# pi3-MotherBoard-rev2.net
KiCad netlist of a schematic drawn in EAGLE
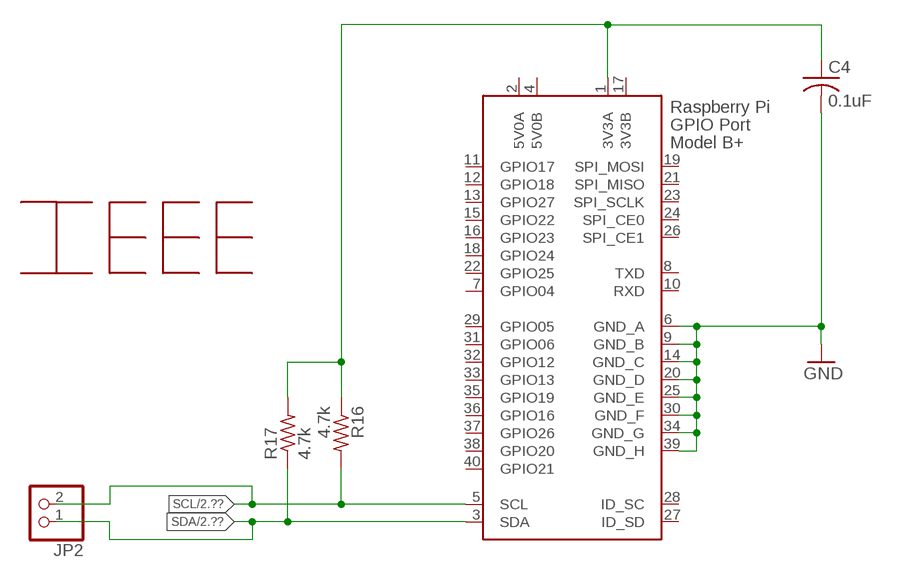
[diagram p0: schematic, sheet 1]
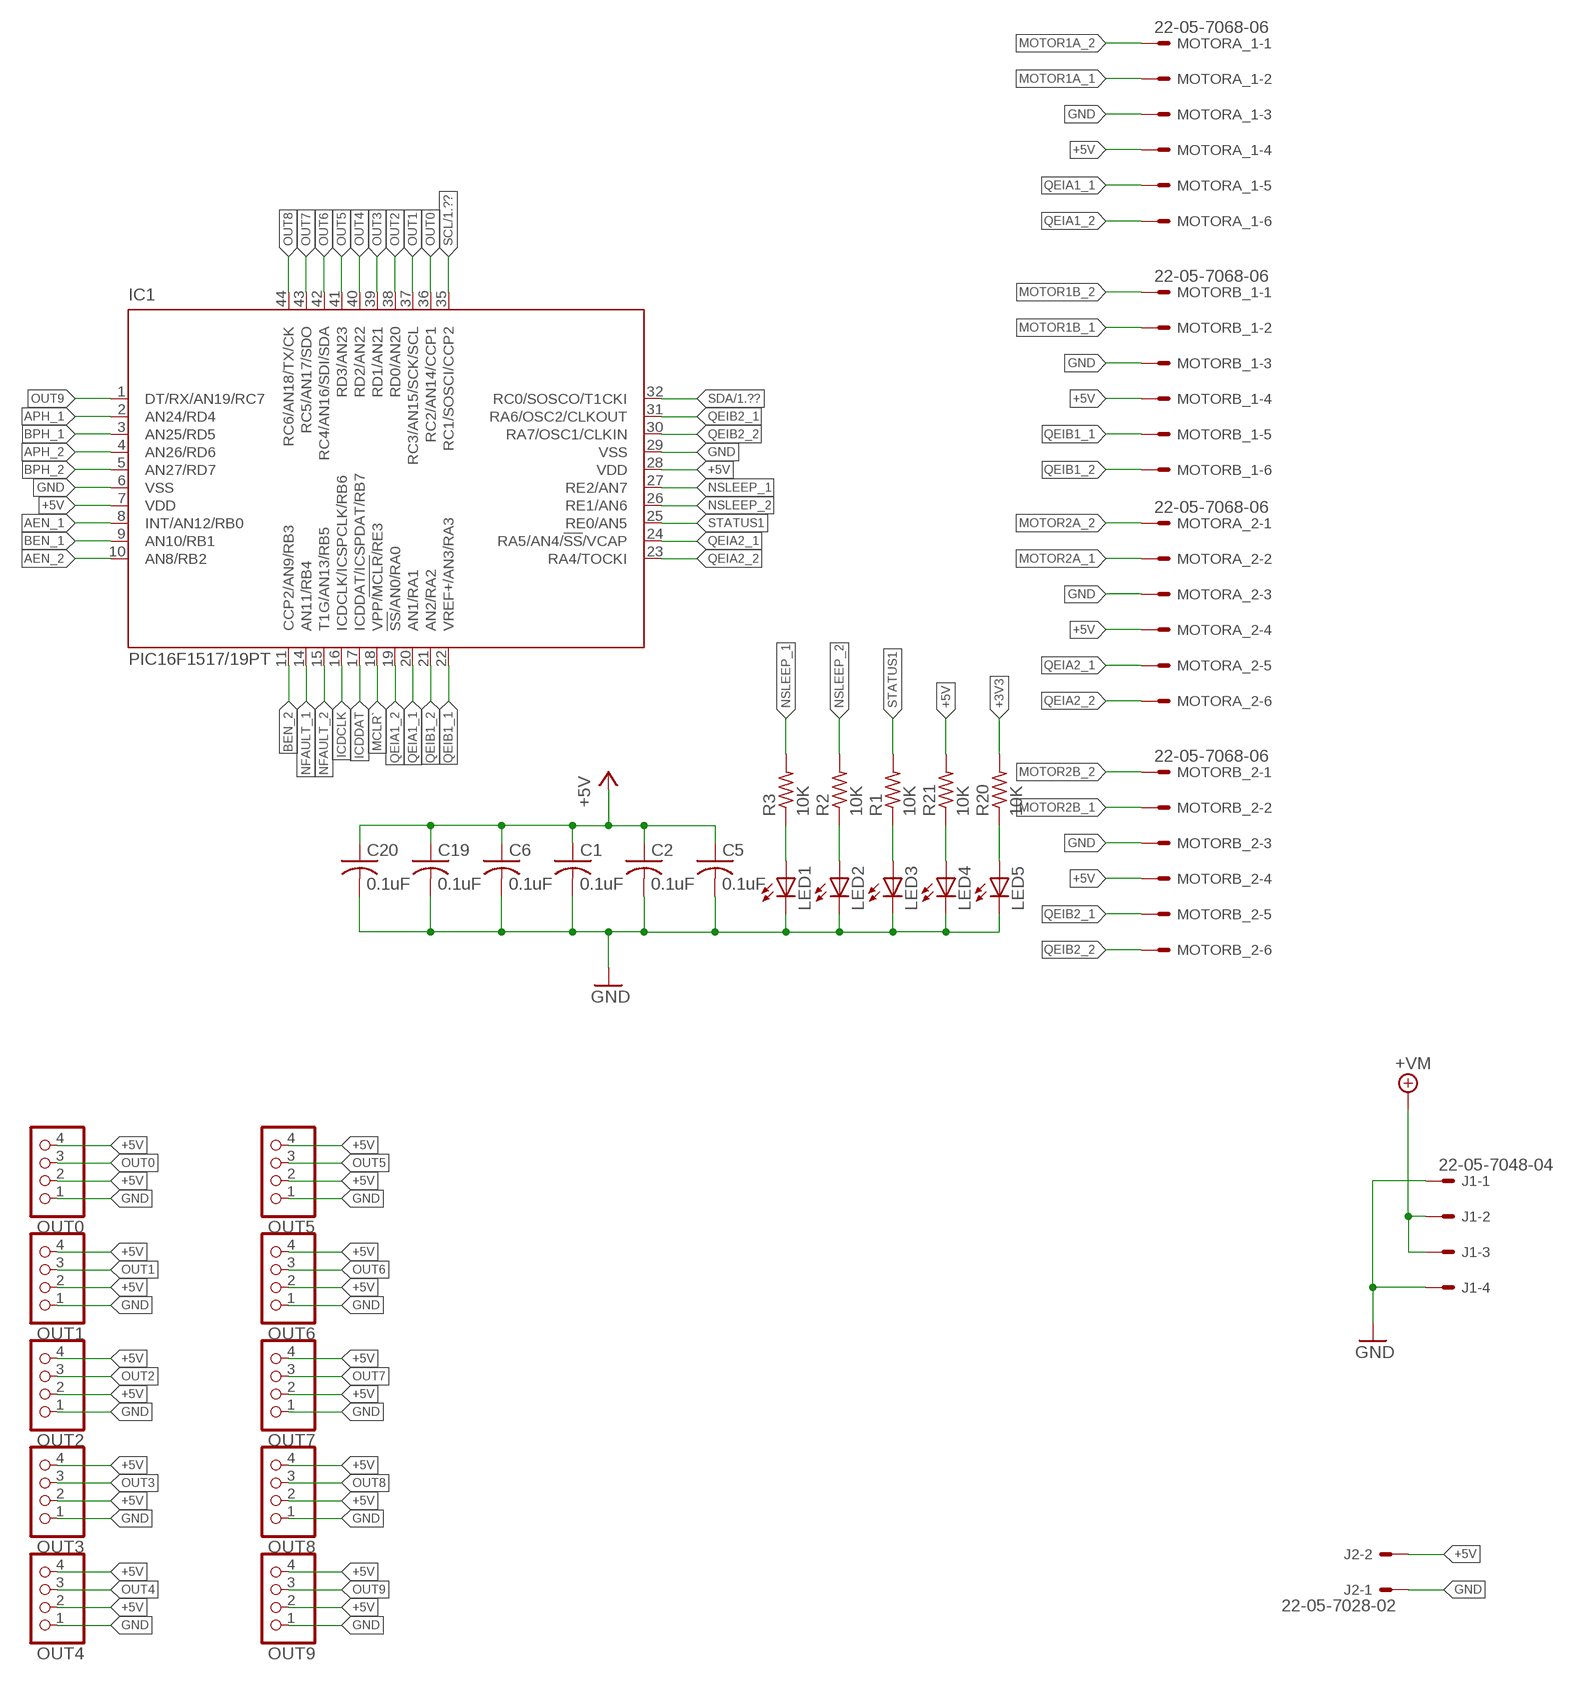
[diagram p1: schematic, sheet 2, part 1 of 2]
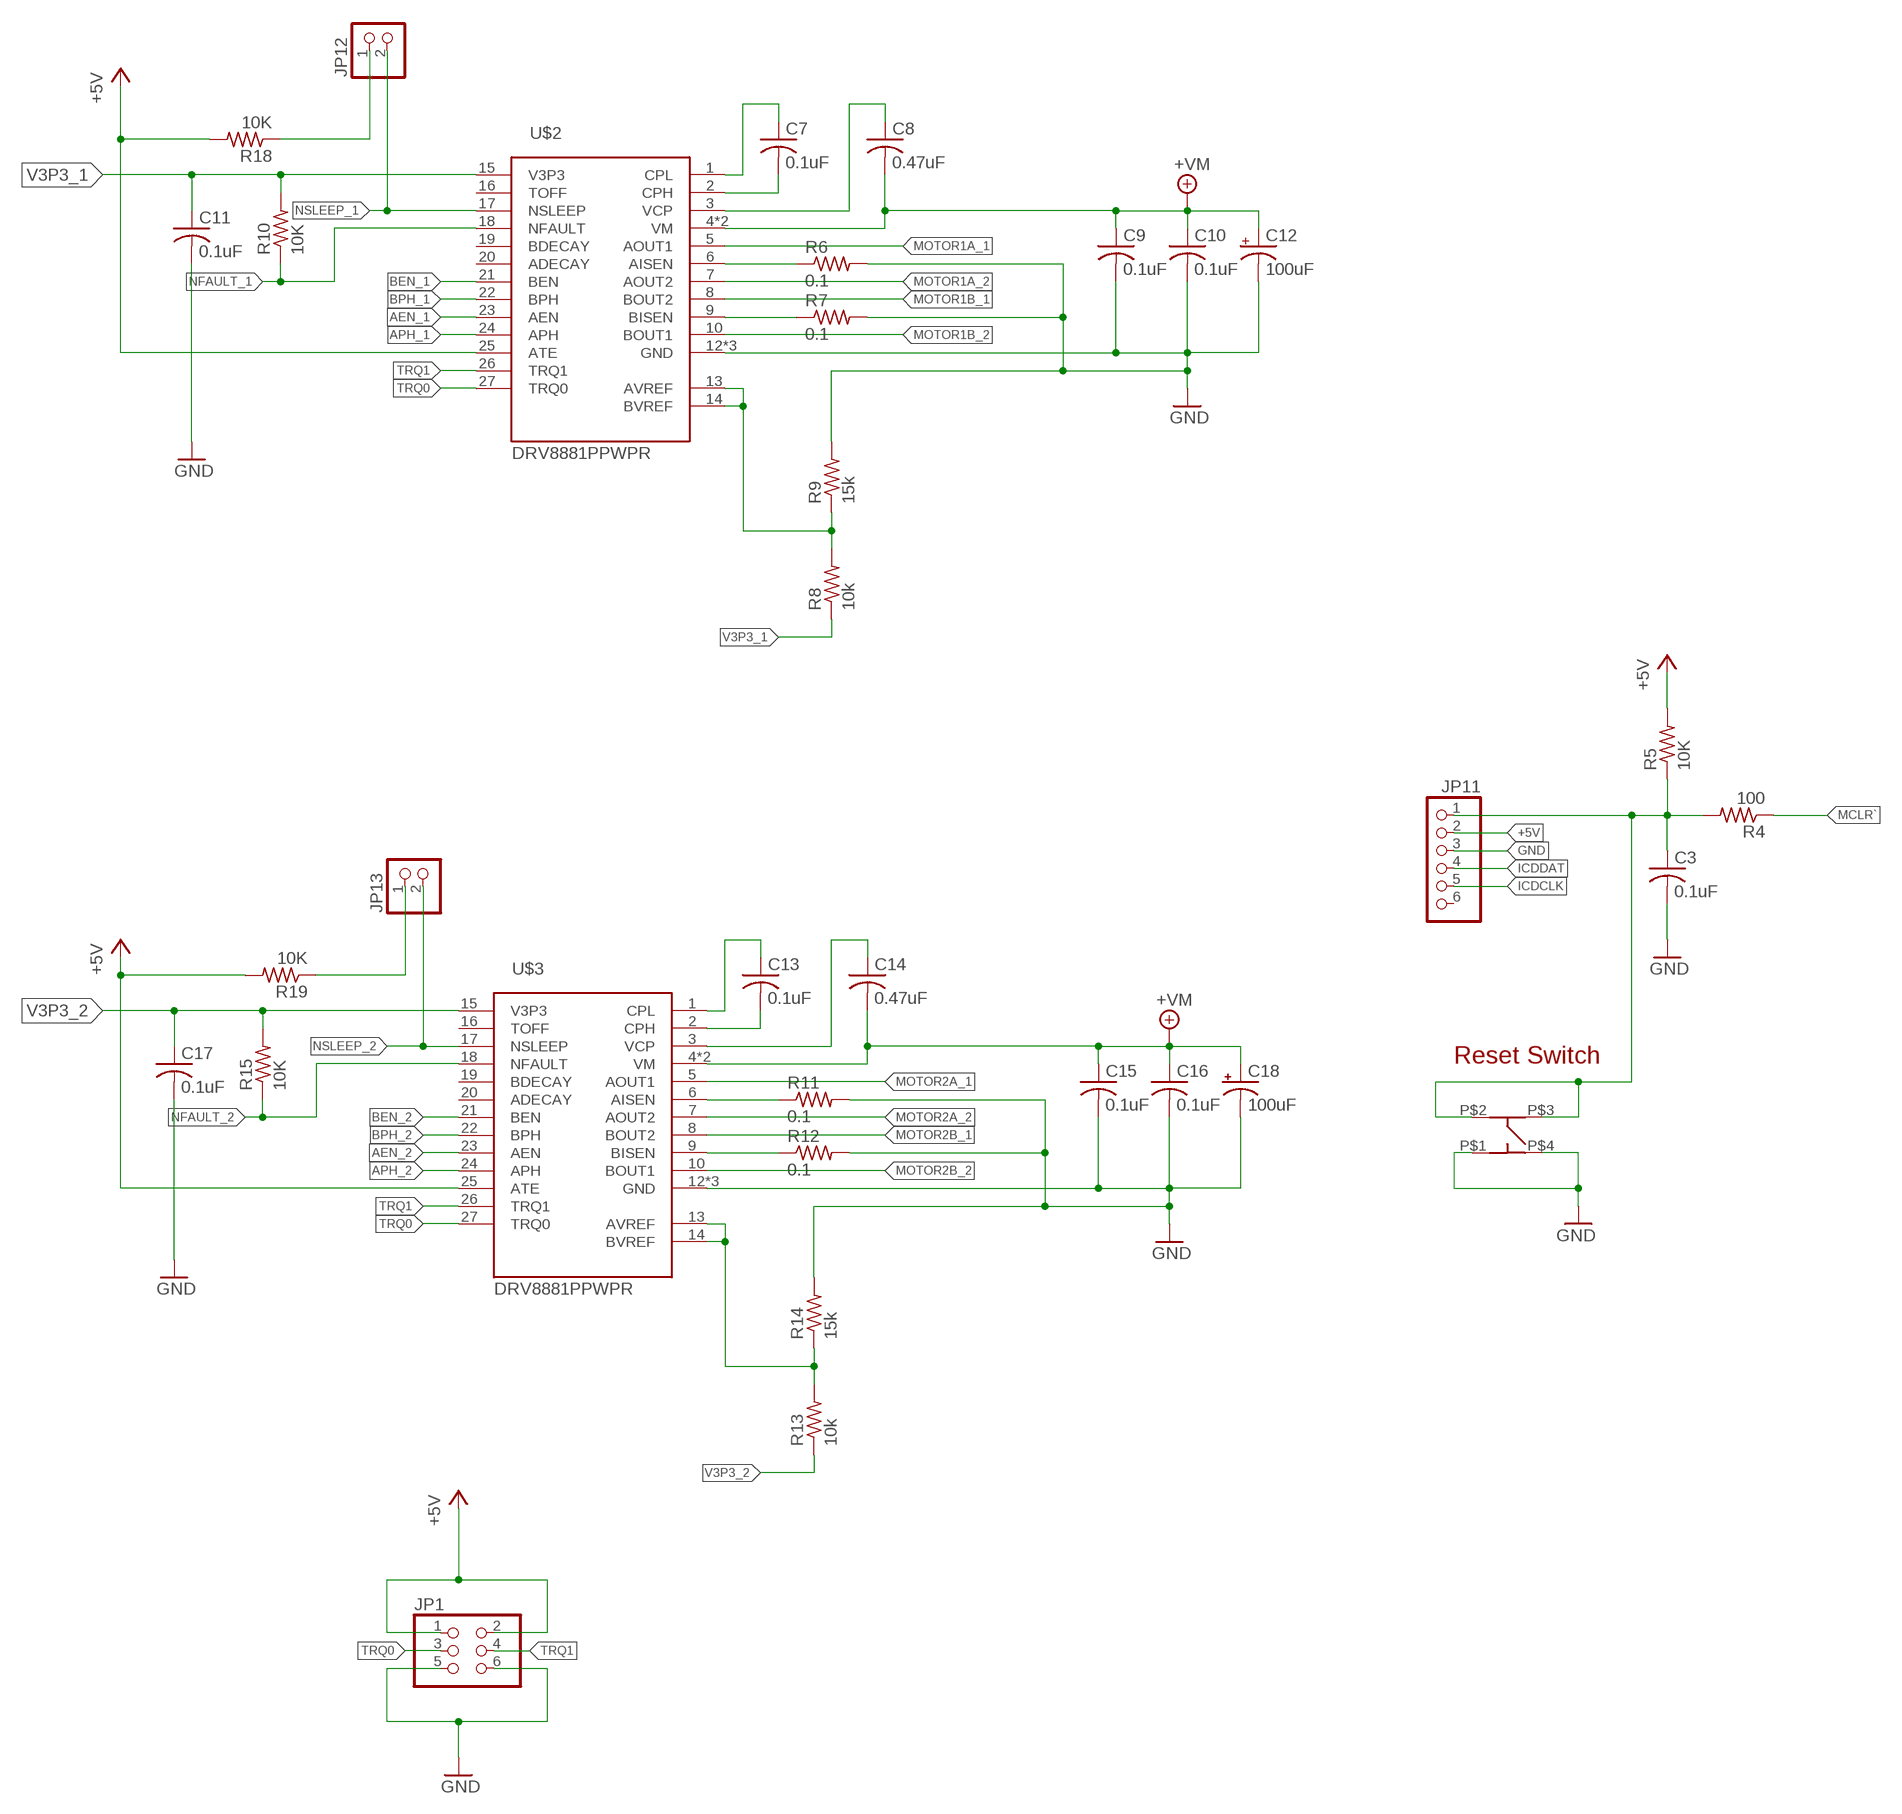
[diagram p2: schematic, sheet 2, part 2 of 2]

(export (version "E")
  (design (tool "Eeschema 10.0.6"))
  (components
    (comp (ref "C4")
      (value "0.1uF")
      (footprint "eagle-import:C0805")
      (libsource (lib "eagle-import") (part "C-USC0805"))
    )
    (comp (ref "JP2")
      (value "PINHD-1X2")
      (footprint "eagle-import:1X02")
      (libsource (lib "eagle-import") (part "PINHD-1X2"))
    )
    (comp (ref "R16")
      (value "4.7k")
      (footprint "eagle-import:R1206")
      (libsource (lib "eagle-import") (part "R-US_R1206"))
    )
    (comp (ref "R17")
      (value "4.7k")
      (footprint "eagle-import:R1206")
      (libsource (lib "eagle-import") (part "R-US_R1206"))
    )
    (comp (ref "U$1")
      (value "LOGO")
      (footprint "eagle-import:IEEE-LOGO")
      (libsource (lib "eagle-import") (part "LOGO"))
    )
    (comp (ref "X1")
      (value "RASPI_BOARD_B+#_FP")
      (footprint "eagle-import:RASPI_BOARD_B+_FULL_PAD")
      (libsource (lib "eagle-import") (part "RASPI_BOARD_B+#_FP"))
    )
    (comp (ref "C1")
      (value "0.1uF")
      (footprint "eagle-import:C0805")
      (libsource (lib "eagle-import") (part "C-USC0805"))
    )
    (comp (ref "C2")
      (value "0.1uF")
      (footprint "eagle-import:C0805")
      (libsource (lib "eagle-import") (part "C-USC0805"))
    )
    (comp (ref "C3")
      (value "0.1uF")
      (footprint "eagle-import:C0805")
      (libsource (lib "eagle-import") (part "C-USC0805"))
    )
    (comp (ref "C5")
      (value "0.1uF")
      (footprint "eagle-import:C0805")
      (libsource (lib "eagle-import") (part "C-USC0805"))
    )
    (comp (ref "C6")
      (value "0.1uF")
      (footprint "eagle-import:C0805")
      (libsource (lib "eagle-import") (part "C-USC0805"))
    )
    (comp (ref "C7")
      (value "0.1uF")
      (footprint "eagle-import:C0402")
      (libsource (lib "eagle-import") (part "C-USC0402"))
    )
    (comp (ref "C8")
      (value "0.47uF")
      (footprint "eagle-import:C0402")
      (libsource (lib "eagle-import") (part "C-USC0402"))
    )
    (comp (ref "C9")
      (value "0.1uF")
      (footprint "eagle-import:C0402")
      (libsource (lib "eagle-import") (part "C-USC0402"))
    )
    (comp (ref "C10")
      (value "0.1uF")
      (footprint "eagle-import:C0402")
      (libsource (lib "eagle-import") (part "C-USC0402"))
    )
    (comp (ref "C11")
      (value "0.1uF")
      (footprint "eagle-import:C0402")
      (libsource (lib "eagle-import") (part "C-USC0402"))
    )
    (comp (ref "C12")
      (value "100uF")
      (footprint "eagle-import:EIA7343")
      (libsource (lib "eagle-import") (part "100UF-10V-10%(TANT)"))
    )
    (comp (ref "C13")
      (value "0.1uF")
      (footprint "eagle-import:C0402")
      (libsource (lib "eagle-import") (part "C-USC0402"))
    )
    (comp (ref "C14")
      (value "0.47uF")
      (footprint "eagle-import:C0402")
      (libsource (lib "eagle-import") (part "C-USC0402"))
    )
    (comp (ref "C15")
      (value "0.1uF")
      (footprint "eagle-import:C0402")
      (libsource (lib "eagle-import") (part "C-USC0402"))
    )
    (comp (ref "C16")
      (value "0.1uF")
      (footprint "eagle-import:C0402")
      (libsource (lib "eagle-import") (part "C-USC0402"))
    )
    (comp (ref "C17")
      (value "0.1uF")
      (footprint "eagle-import:C0402")
      (libsource (lib "eagle-import") (part "C-USC0402"))
    )
    (comp (ref "C18")
      (value "100uF")
      (footprint "eagle-import:EIA7343")
      (libsource (lib "eagle-import") (part "100UF-10V-10%(TANT)"))
    )
    (comp (ref "C19")
      (value "0.1uF")
      (footprint "eagle-import:C0805")
      (libsource (lib "eagle-import") (part "C-USC0805"))
    )
    (comp (ref "C20")
      (value "0.1uF")
      (footprint "eagle-import:C0805")
      (libsource (lib "eagle-import") (part "C-USC0805"))
    )
    (comp (ref "IC1")
      (value "PIC16F1517/19PT")
      (footprint "eagle-import:TQFP44")
      (libsource (lib "eagle-import") (part "PIC16F1517/19PT"))
    )
    (comp (ref "J1")
      (value "22-05-7048-04")
      (footprint "eagle-import:7395-04")
      (libsource (lib "eagle-import") (part "22-?-0405-7048"))
    )
    (comp (ref "J2")
      (value "22-05-7028-02")
      (footprint "eagle-import:7395-02")
      (libsource (lib "eagle-import") (part "22-?-0205-7028"))
    )
    (comp (ref "JP1")
      (value "PINHD-2X3")
      (footprint "eagle-import:2X03")
      (libsource (lib "eagle-import") (part "PINHD-2X3"))
    )
    (comp (ref "JP11")
      (value "PINHD-1X6/90")
      (footprint "eagle-import:1X06_90")
      (libsource (lib "eagle-import") (part "PINHD-1X6/90"))
    )
    (comp (ref "JP12")
      (value "PINHD-1X2")
      (footprint "eagle-import:1X02")
      (libsource (lib "eagle-import") (part "PINHD-1X2"))
    )
    (comp (ref "JP13")
      (value "PINHD-1X2")
      (footprint "eagle-import:1X02")
      (libsource (lib "eagle-import") (part "PINHD-1X2"))
    )
    (comp (ref "LED1")
      (value "LEDSML0603")
      (footprint "eagle-import:SML0603")
      (libsource (lib "eagle-import") (part "LEDSML0603"))
    )
    (comp (ref "LED2")
      (value "LEDSML0603")
      (footprint "eagle-import:SML0603")
      (libsource (lib "eagle-import") (part "LEDSML0603"))
    )
    (comp (ref "LED3")
      (value "LEDSML0603")
      (footprint "eagle-import:SML0603")
      (libsource (lib "eagle-import") (part "LEDSML0603"))
    )
    (comp (ref "LED4")
      (value "LEDSML0603")
      (footprint "eagle-import:SML0603")
      (libsource (lib "eagle-import") (part "LEDSML0603"))
    )
    (comp (ref "LED5")
      (value "LEDSML0603")
      (footprint "eagle-import:SML0603")
      (libsource (lib "eagle-import") (part "LEDSML0603"))
    )
    (comp (ref "MOTORA_1")
      (value "22-05-7068-06")
      (footprint "eagle-import:7395-06")
      (libsource (lib "eagle-import") (part "22-?-0605-7068"))
    )
    (comp (ref "MOTORA_2")
      (value "22-05-7068-06")
      (footprint "eagle-import:7395-06")
      (libsource (lib "eagle-import") (part "22-?-0605-7068"))
    )
    (comp (ref "MOTORB_1")
      (value "22-05-7068-06")
      (footprint "eagle-import:7395-06")
      (libsource (lib "eagle-import") (part "22-?-0605-7068"))
    )
    (comp (ref "MOTORB_2")
      (value "22-05-7068-06")
      (footprint "eagle-import:7395-06")
      (libsource (lib "eagle-import") (part "22-?-0605-7068"))
    )
    (comp (ref "OUT0")
      (value "PINHD-1X4")
      (footprint "eagle-import:1X04")
      (libsource (lib "eagle-import") (part "PINHD-1X4"))
    )
    (comp (ref "OUT1")
      (value "PINHD-1X4")
      (footprint "eagle-import:1X04")
      (libsource (lib "eagle-import") (part "PINHD-1X4"))
    )
    (comp (ref "OUT2")
      (value "PINHD-1X4")
      (footprint "eagle-import:1X04")
      (libsource (lib "eagle-import") (part "PINHD-1X4"))
    )
    (comp (ref "OUT3")
      (value "PINHD-1X4")
      (footprint "eagle-import:1X04")
      (libsource (lib "eagle-import") (part "PINHD-1X4"))
    )
    (comp (ref "OUT4")
      (value "PINHD-1X4")
      (footprint "eagle-import:1X04")
      (libsource (lib "eagle-import") (part "PINHD-1X4"))
    )
    (comp (ref "OUT5")
      (value "PINHD-1X4")
      (footprint "eagle-import:1X04")
      (libsource (lib "eagle-import") (part "PINHD-1X4"))
    )
    (comp (ref "OUT6")
      (value "PINHD-1X4")
      (footprint "eagle-import:1X04")
      (libsource (lib "eagle-import") (part "PINHD-1X4"))
    )
    (comp (ref "OUT7")
      (value "PINHD-1X4")
      (footprint "eagle-import:1X04")
      (libsource (lib "eagle-import") (part "PINHD-1X4"))
    )
    (comp (ref "OUT8")
      (value "PINHD-1X4")
      (footprint "eagle-import:1X04")
      (libsource (lib "eagle-import") (part "PINHD-1X4"))
    )
    (comp (ref "OUT9")
      (value "PINHD-1X4")
      (footprint "eagle-import:1X04")
      (libsource (lib "eagle-import") (part "PINHD-1X4"))
    )
    (comp (ref "R1")
      (value "10K")
      (footprint "eagle-import:R1206")
      (libsource (lib "eagle-import") (part "R-US_R1206"))
    )
    (comp (ref "R2")
      (value "10K")
      (footprint "eagle-import:R1206")
      (libsource (lib "eagle-import") (part "R-US_R1206"))
    )
    (comp (ref "R3")
      (value "10K")
      (footprint "eagle-import:R1206")
      (libsource (lib "eagle-import") (part "R-US_R1206"))
    )
    (comp (ref "R4")
      (value "100")
      (footprint "eagle-import:R1206")
      (libsource (lib "eagle-import") (part "R-US_R1206"))
    )
    (comp (ref "R5")
      (value "10K")
      (footprint "eagle-import:R1206")
      (libsource (lib "eagle-import") (part "R-US_R1206"))
    )
    (comp (ref "R6")
      (value "0.1")
      (footprint "eagle-import:R1206")
      (libsource (lib "eagle-import") (part "R-US_R1206"))
    )
    (comp (ref "R7")
      (value "0.1")
      (footprint "eagle-import:R1206")
      (libsource (lib "eagle-import") (part "R-US_R1206"))
    )
    (comp (ref "R8")
      (value "10k")
      (footprint "eagle-import:R0402")
      (libsource (lib "eagle-import") (part "R-US_R0402"))
    )
    (comp (ref "R9")
      (value "15k")
      (footprint "eagle-import:R0402")
      (libsource (lib "eagle-import") (part "R-US_R0402"))
    )
    (comp (ref "R10")
      (value "10K")
      (footprint "eagle-import:R1206")
      (libsource (lib "eagle-import") (part "R-US_R1206"))
    )
    (comp (ref "R11")
      (value "0.1")
      (footprint "eagle-import:R1206")
      (libsource (lib "eagle-import") (part "R-US_R1206"))
    )
    (comp (ref "R12")
      (value "0.1")
      (footprint "eagle-import:R1206")
      (libsource (lib "eagle-import") (part "R-US_R1206"))
    )
    (comp (ref "R13")
      (value "10k")
      (footprint "eagle-import:R0402")
      (libsource (lib "eagle-import") (part "R-US_R0402"))
    )
    (comp (ref "R14")
      (value "15k")
      (footprint "eagle-import:R0402")
      (libsource (lib "eagle-import") (part "R-US_R0402"))
    )
    (comp (ref "R15")
      (value "10K")
      (footprint "eagle-import:R1206")
      (libsource (lib "eagle-import") (part "R-US_R1206"))
    )
    (comp (ref "R18")
      (value "10K")
      (footprint "eagle-import:R1206")
      (libsource (lib "eagle-import") (part "R-US_R1206"))
    )
    (comp (ref "R19")
      (value "10K")
      (footprint "eagle-import:R1206")
      (libsource (lib "eagle-import") (part "R-US_R1206"))
    )
    (comp (ref "R20")
      (value "10K")
      (footprint "eagle-import:R1206")
      (libsource (lib "eagle-import") (part "R-US_R1206"))
    )
    (comp (ref "R21")
      (value "10K")
      (footprint "eagle-import:R1206")
      (libsource (lib "eagle-import") (part "R-US_R1206"))
    )
    (comp (ref "TOUCH_RESET")
      (value "RESET")
      (footprint "eagle-import:MC32882_FINAL")
      (libsource (lib "eagle-import") (part "MC32882_SW"))
    )
    (comp (ref "U$2")
      (value "DRV8881PPWPR")
      (footprint "eagle-import:TSSOP-28")
      (libsource (lib "eagle-import") (part "DRV8881PPWPR"))
    )
    (comp (ref "U$3")
      (value "DRV8881PPWPR")
      (footprint "eagle-import:TSSOP-28")
      (libsource (lib "eagle-import") (part "DRV8881PPWPR"))
    )
  )
  (nets
    (net (code "1") (name "+3V3") (class "Default")
      (node (ref "C4") (pin "1") (pinfunction "1_1") (pintype "passive"))
      (node (ref "R16") (pin "1") (pinfunction "1_1") (pintype "passive"))
      (node (ref "R17") (pin "2") (pinfunction "2_2") (pintype "passive"))
      (node (ref "R20") (pin "2") (pinfunction "2_2") (pintype "passive"))
      (node (ref "X1") (pin "1") (pinfunction "3V3A_1") (pintype "power_in"))
    )
    (net (code "2") (name "+5V") (class "Default")
      (node (ref "C1") (pin "1") (pinfunction "1_1") (pintype "passive"))
      (node (ref "C19") (pin "1") (pinfunction "1_1") (pintype "passive"))
      (node (ref "C2") (pin "1") (pinfunction "1_1") (pintype "passive"))
      (node (ref "C20") (pin "1") (pinfunction "1_1") (pintype "passive"))
      (node (ref "C5") (pin "1") (pinfunction "1_1") (pintype "passive"))
      (node (ref "C6") (pin "1") (pinfunction "1_1") (pintype "passive"))
      (node (ref "IC1") (pin "28") (pinfunction "VDD_28") (pintype "power_in"))
      (node (ref "IC1") (pin "7") (pinfunction "VDD_7") (pintype "power_in"))
      (node (ref "J2") (pin "2") (pinfunction "S_2") (pintype "passive"))
      (node (ref "JP1") (pin "1") (pinfunction "1_1") (pintype "passive"))
      (node (ref "JP1") (pin "2") (pinfunction "2_2") (pintype "passive"))
      (node (ref "JP11") (pin "2") (pinfunction "2_2") (pintype "passive"))
      (node (ref "MOTORA_1") (pin "4") (pinfunction "S_4") (pintype "passive"))
      (node (ref "MOTORA_2") (pin "4") (pinfunction "S_4") (pintype "passive"))
      (node (ref "MOTORB_1") (pin "4") (pinfunction "S_4") (pintype "passive"))
      (node (ref "MOTORB_2") (pin "4") (pinfunction "S_4") (pintype "passive"))
      (node (ref "OUT0") (pin "2") (pinfunction "2_2") (pintype "passive"))
      (node (ref "OUT0") (pin "4") (pinfunction "4_4") (pintype "passive"))
      (node (ref "OUT1") (pin "2") (pinfunction "2_2") (pintype "passive"))
      (node (ref "OUT1") (pin "4") (pinfunction "4_4") (pintype "passive"))
      (node (ref "OUT2") (pin "2") (pinfunction "2_2") (pintype "passive"))
      (node (ref "OUT2") (pin "4") (pinfunction "4_4") (pintype "passive"))
      (node (ref "OUT3") (pin "2") (pinfunction "2_2") (pintype "passive"))
      (node (ref "OUT3") (pin "4") (pinfunction "4_4") (pintype "passive"))
      (node (ref "OUT4") (pin "2") (pinfunction "2_2") (pintype "passive"))
      (node (ref "OUT4") (pin "4") (pinfunction "4_4") (pintype "passive"))
      (node (ref "OUT5") (pin "2") (pinfunction "2_2") (pintype "passive"))
      (node (ref "OUT5") (pin "4") (pinfunction "4_4") (pintype "passive"))
      (node (ref "OUT6") (pin "2") (pinfunction "2_2") (pintype "passive"))
      (node (ref "OUT6") (pin "4") (pinfunction "4_4") (pintype "passive"))
      (node (ref "OUT7") (pin "2") (pinfunction "2_2") (pintype "passive"))
      (node (ref "OUT7") (pin "4") (pinfunction "4_4") (pintype "passive"))
      (node (ref "OUT8") (pin "2") (pinfunction "2_2") (pintype "passive"))
      (node (ref "OUT8") (pin "4") (pinfunction "4_4") (pintype "passive"))
      (node (ref "OUT9") (pin "2") (pinfunction "2_2") (pintype "passive"))
      (node (ref "OUT9") (pin "4") (pinfunction "4_4") (pintype "passive"))
      (node (ref "R18") (pin "2") (pinfunction "2_2") (pintype "passive"))
      (node (ref "R19") (pin "2") (pinfunction "2_2") (pintype "passive"))
      (node (ref "R21") (pin "2") (pinfunction "2_2") (pintype "passive"))
      (node (ref "R5") (pin "2") (pinfunction "2_2") (pintype "passive"))
      (node (ref "U$2") (pin "25") (pinfunction "ATE_25") (pintype "bidirectional"))
      (node (ref "U$3") (pin "25") (pinfunction "ATE_25") (pintype "bidirectional"))
    )
    (net (code "3") (name "+7V") (class "Default")
      (node (ref "C10") (pin "1") (pinfunction "1_1") (pintype "passive"))
      (node (ref "C12") (pin "A") (pinfunction "+_A") (pintype "passive"))
      (node (ref "C14") (pin "2") (pinfunction "2_2") (pintype "passive"))
      (node (ref "C15") (pin "1") (pinfunction "1_1") (pintype "passive"))
      (node (ref "C16") (pin "1") (pinfunction "1_1") (pintype "passive"))
      (node (ref "C18") (pin "A") (pinfunction "+_A") (pintype "passive"))
      (node (ref "C8") (pin "2") (pinfunction "2_2") (pintype "passive"))
      (node (ref "C9") (pin "1") (pinfunction "1_1") (pintype "passive"))
      (node (ref "J1") (pin "2") (pinfunction "S_2") (pintype "passive"))
      (node (ref "J1") (pin "3") (pinfunction "S_3") (pintype "passive"))
      (node (ref "U$2") (pin "11") (pinfunction "VM_11") (pintype "bidirectional"))
      (node (ref "U$2") (pin "4") (pinfunction "VM_4") (pintype "bidirectional"))
      (node (ref "U$3") (pin "11") (pinfunction "VM_11") (pintype "bidirectional"))
      (node (ref "U$3") (pin "4") (pinfunction "VM_4") (pintype "bidirectional"))
    )
    (net (code "4") (name "3V3B") (class "Default")
      (node (ref "X1") (pin "17") (pinfunction "3V3B_17") (pintype "power_in"))
    )
    (net (code "5") (name "5V0A") (class "Default")
      (node (ref "X1") (pin "2") (pinfunction "5V0A_2") (pintype "power_in"))
    )
    (net (code "6") (name "5V0B") (class "Default")
      (node (ref "X1") (pin "4") (pinfunction "5V0B_4") (pintype "power_in"))
    )
    (net (code "7") (name "AEN_1") (class "Default")
      (node (ref "IC1") (pin "8") (pinfunction "INT/AN12/RB0_8") (pintype "bidirectional"))
      (node (ref "U$2") (pin "23") (pinfunction "AEN_23") (pintype "bidirectional"))
    )
    (net (code "8") (name "AEN_2") (class "Default")
      (node (ref "IC1") (pin "10") (pinfunction "AN8/RB2_10") (pintype "bidirectional"))
      (node (ref "U$3") (pin "23") (pinfunction "AEN_23") (pintype "bidirectional"))
    )
    (net (code "9") (name "APH_1") (class "Default")
      (node (ref "IC1") (pin "2") (pinfunction "AN24/RD4_2") (pintype "bidirectional"))
      (node (ref "U$2") (pin "24") (pinfunction "APH_24") (pintype "bidirectional"))
    )
    (net (code "10") (name "APH_2") (class "Default")
      (node (ref "IC1") (pin "4") (pinfunction "AN26/RD6_4") (pintype "bidirectional"))
      (node (ref "U$3") (pin "24") (pinfunction "APH_24") (pintype "bidirectional"))
    )
    (net (code "11") (name "BEN_1") (class "Default")
      (node (ref "IC1") (pin "9") (pinfunction "AN10/RB1_9") (pintype "bidirectional"))
      (node (ref "U$2") (pin "21") (pinfunction "BEN_21") (pintype "bidirectional"))
    )
    (net (code "12") (name "BEN_2") (class "Default")
      (node (ref "IC1") (pin "11") (pinfunction "CCP2/AN9/RB3_11") (pintype "bidirectional"))
      (node (ref "U$3") (pin "21") (pinfunction "BEN_21") (pintype "bidirectional"))
    )
    (net (code "13") (name "BPH_1") (class "Default")
      (node (ref "IC1") (pin "3") (pinfunction "AN25/RD5_3") (pintype "bidirectional"))
      (node (ref "U$2") (pin "22") (pinfunction "BPH_22") (pintype "bidirectional"))
    )
    (net (code "14") (name "BPH_2") (class "Default")
      (node (ref "IC1") (pin "5") (pinfunction "AN27/RD7_5") (pintype "bidirectional"))
      (node (ref "U$3") (pin "22") (pinfunction "BPH_22") (pintype "bidirectional"))
    )
    (net (code "15") (name "GND") (class "Default")
      (node (ref "C1") (pin "2") (pinfunction "2_2") (pintype "passive"))
      (node (ref "C10") (pin "2") (pinfunction "2_2") (pintype "passive"))
      (node (ref "C11") (pin "2") (pinfunction "2_2") (pintype "passive"))
      (node (ref "C12") (pin "C") (pinfunction "-_C") (pintype "passive"))
      (node (ref "C15") (pin "2") (pinfunction "2_2") (pintype "passive"))
      (node (ref "C16") (pin "2") (pinfunction "2_2") (pintype "passive"))
      (node (ref "C17") (pin "2") (pinfunction "2_2") (pintype "passive"))
      (node (ref "C18") (pin "C") (pinfunction "-_C") (pintype "passive"))
      (node (ref "C19") (pin "2") (pinfunction "2_2") (pintype "passive"))
      (node (ref "C2") (pin "2") (pinfunction "2_2") (pintype "passive"))
      (node (ref "C20") (pin "2") (pinfunction "2_2") (pintype "passive"))
      (node (ref "C3") (pin "2") (pinfunction "2_2") (pintype "passive"))
      (node (ref "C4") (pin "2") (pinfunction "2_2") (pintype "passive"))
      (node (ref "C5") (pin "2") (pinfunction "2_2") (pintype "passive"))
      (node (ref "C6") (pin "2") (pinfunction "2_2") (pintype "passive"))
      (node (ref "C9") (pin "2") (pinfunction "2_2") (pintype "passive"))
      (node (ref "IC1") (pin "29") (pinfunction "VSS_29") (pintype "power_in"))
      (node (ref "IC1") (pin "6") (pinfunction "VSS_6") (pintype "power_in"))
      (node (ref "J1") (pin "1") (pinfunction "S_1") (pintype "passive"))
      (node (ref "J1") (pin "4") (pinfunction "S_4") (pintype "passive"))
      (node (ref "J2") (pin "1") (pinfunction "S_1") (pintype "passive"))
      (node (ref "JP1") (pin "5") (pinfunction "5_5") (pintype "passive"))
      (node (ref "JP1") (pin "6") (pinfunction "6_6") (pintype "passive"))
      (node (ref "JP11") (pin "3") (pinfunction "3_3") (pintype "passive"))
      (node (ref "LED1") (pin "C") (pinfunction "C_C") (pintype "passive"))
      (node (ref "LED2") (pin "C") (pinfunction "C_C") (pintype "passive"))
      (node (ref "LED3") (pin "C") (pinfunction "C_C") (pintype "passive"))
      (node (ref "LED4") (pin "C") (pinfunction "C_C") (pintype "passive"))
      (node (ref "LED5") (pin "C") (pinfunction "C_C") (pintype "passive"))
      (node (ref "MOTORA_1") (pin "3") (pinfunction "S_3") (pintype "passive"))
      (node (ref "MOTORA_2") (pin "3") (pinfunction "S_3") (pintype "passive"))
      (node (ref "MOTORB_1") (pin "3") (pinfunction "S_3") (pintype "passive"))
      (node (ref "MOTORB_2") (pin "3") (pinfunction "S_3") (pintype "passive"))
      (node (ref "OUT0") (pin "1") (pinfunction "1_1") (pintype "passive"))
      (node (ref "OUT1") (pin "1") (pinfunction "1_1") (pintype "passive"))
      (node (ref "OUT2") (pin "1") (pinfunction "1_1") (pintype "passive"))
      (node (ref "OUT3") (pin "1") (pinfunction "1_1") (pintype "passive"))
      (node (ref "OUT4") (pin "1") (pinfunction "1_1") (pintype "passive"))
      (node (ref "OUT5") (pin "1") (pinfunction "1_1") (pintype "passive"))
      (node (ref "OUT6") (pin "1") (pinfunction "1_1") (pintype "passive"))
      (node (ref "OUT7") (pin "1") (pinfunction "1_1") (pintype "passive"))
      (node (ref "OUT8") (pin "1") (pinfunction "1_1") (pintype "passive"))
      (node (ref "OUT9") (pin "1") (pinfunction "1_1") (pintype "passive"))
      (node (ref "R11") (pin "2") (pinfunction "2_2") (pintype "passive"))
      (node (ref "R12") (pin "2") (pinfunction "2_2") (pintype "passive"))
      (node (ref "R14") (pin "2") (pinfunction "2_2") (pintype "passive"))
      (node (ref "R6") (pin "2") (pinfunction "2_2") (pintype "passive"))
      (node (ref "R7") (pin "2") (pinfunction "2_2") (pintype "passive"))
      (node (ref "R9") (pin "2") (pinfunction "2_2") (pintype "passive"))
      (node (ref "TOUCH_RESET") (pin "P$1") (pinfunction "P1_P$1") (pintype "bidirectional"))
      (node (ref "TOUCH_RESET") (pin "P$4") (pinfunction "P4_P$4") (pintype "bidirectional"))
      (node (ref "U$2") (pin "12") (pinfunction "GND_12") (pintype "bidirectional"))
      (node (ref "U$2") (pin "28") (pinfunction "GND_28") (pintype "bidirectional"))
      (node (ref "U$2") (pin "EXP") (pinfunction "GND_EXP") (pintype "bidirectional"))
      (node (ref "U$3") (pin "12") (pinfunction "GND_12") (pintype "bidirectional"))
      (node (ref "U$3") (pin "28") (pinfunction "GND_28") (pintype "bidirectional"))
      (node (ref "U$3") (pin "EXP") (pinfunction "GND_EXP") (pintype "bidirectional"))
      (node (ref "X1") (pin "14") (pinfunction "GND_C_14") (pintype "power_in"))
      (node (ref "X1") (pin "20") (pinfunction "GND_D_20") (pintype "power_in"))
      (node (ref "X1") (pin "25") (pinfunction "GND_E_25") (pintype "power_in"))
      (node (ref "X1") (pin "30") (pinfunction "GND_F_30") (pintype "power_in"))
      (node (ref "X1") (pin "34") (pinfunction "GND_G_34") (pintype "power_in"))
      (node (ref "X1") (pin "39") (pinfunction "GND_H_39") (pintype "power_in"))
      (node (ref "X1") (pin "6") (pinfunction "GND_A_6") (pintype "power_in"))
      (node (ref "X1") (pin "9") (pinfunction "GND_B_9") (pintype "power_in"))
    )
    (net (code "16") (name "ICDCLK") (class "Default")
      (node (ref "IC1") (pin "16") (pinfunction "ICDCLK/ICSPCLK/RB6_16") (pintype "bidirectional"))
      (node (ref "JP11") (pin "5") (pinfunction "5_5") (pintype "passive"))
    )
    (net (code "17") (name "ICDDAT") (class "Default")
      (node (ref "IC1") (pin "17") (pinfunction "ICDDAT/ICSPDAT/RB7_17") (pintype "bidirectional"))
      (node (ref "JP11") (pin "4") (pinfunction "4_4") (pintype "passive"))
    )
    (net (code "18") (name "MCLR`") (class "Default")
      (node (ref "IC1") (pin "18") (pinfunction "VPP/~{MCLR}/RE3_18") (pintype "input"))
      (node (ref "R4") (pin "1") (pinfunction "1_1") (pintype "passive"))
    )
    (net (code "19") (name "MOTOR1A_1") (class "Default")
      (node (ref "MOTORA_1") (pin "2") (pinfunction "S_2") (pintype "passive"))
      (node (ref "U$2") (pin "5") (pinfunction "AOUT1_5") (pintype "bidirectional"))
    )
    (net (code "20") (name "MOTOR1A_2") (class "Default")
      (node (ref "MOTORA_1") (pin "1") (pinfunction "S_1") (pintype "passive"))
      (node (ref "U$2") (pin "7") (pinfunction "AOUT2_7") (pintype "bidirectional"))
    )
    (net (code "21") (name "MOTOR1B_1") (class "Default")
      (node (ref "MOTORB_1") (pin "2") (pinfunction "S_2") (pintype "passive"))
      (node (ref "U$2") (pin "8") (pinfunction "BOUT2_8") (pintype "bidirectional"))
    )
    (net (code "22") (name "MOTOR1B_2") (class "Default")
      (node (ref "MOTORB_1") (pin "1") (pinfunction "S_1") (pintype "passive"))
      (node (ref "U$2") (pin "10") (pinfunction "BOUT1_10") (pintype "bidirectional"))
    )
    (net (code "23") (name "MOTOR2A_1") (class "Default")
      (node (ref "MOTORA_2") (pin "2") (pinfunction "S_2") (pintype "passive"))
      (node (ref "U$3") (pin "5") (pinfunction "AOUT1_5") (pintype "bidirectional"))
    )
    (net (code "24") (name "MOTOR2A_2") (class "Default")
      (node (ref "MOTORA_2") (pin "1") (pinfunction "S_1") (pintype "passive"))
      (node (ref "U$3") (pin "7") (pinfunction "AOUT2_7") (pintype "bidirectional"))
    )
    (net (code "25") (name "MOTOR2B_1") (class "Default")
      (node (ref "MOTORB_2") (pin "2") (pinfunction "S_2") (pintype "passive"))
      (node (ref "U$3") (pin "8") (pinfunction "BOUT2_8") (pintype "bidirectional"))
    )
    (net (code "26") (name "MOTOR2B_2") (class "Default")
      (node (ref "MOTORB_2") (pin "1") (pinfunction "S_1") (pintype "passive"))
      (node (ref "U$3") (pin "10") (pinfunction "BOUT1_10") (pintype "bidirectional"))
    )
    (net (code "27") (name "NFAULT_1") (class "Default")
      (node (ref "IC1") (pin "14") (pinfunction "AN11/RB4_14") (pintype "bidirectional"))
      (node (ref "R10") (pin "1") (pinfunction "1_1") (pintype "passive"))
      (node (ref "U$2") (pin "18") (pinfunction "NFAULT_18") (pintype "bidirectional"))
    )
    (net (code "28") (name "NFAULT_2") (class "Default")
      (node (ref "IC1") (pin "15") (pinfunction "T1G/AN13/RB5_15") (pintype "bidirectional"))
      (node (ref "R15") (pin "1") (pinfunction "1_1") (pintype "passive"))
      (node (ref "U$3") (pin "18") (pinfunction "NFAULT_18") (pintype "bidirectional"))
    )
    (net (code "29") (name "NSLEEP_1") (class "Default")
      (node (ref "IC1") (pin "27") (pinfunction "RE2/AN7_27") (pintype "bidirectional"))
      (node (ref "JP12") (pin "2") (pinfunction "2_2") (pintype "passive"))
      (node (ref "R3") (pin "2") (pinfunction "2_2") (pintype "passive"))
      (node (ref "U$2") (pin "17") (pinfunction "NSLEEP_17") (pintype "bidirectional"))
    )
    (net (code "30") (name "NSLEEP_2") (class "Default")
      (node (ref "IC1") (pin "26") (pinfunction "RE1/AN6_26") (pintype "bidirectional"))
      (node (ref "JP13") (pin "2") (pinfunction "2_2") (pintype "passive"))
      (node (ref "R2") (pin "2") (pinfunction "2_2") (pintype "passive"))
      (node (ref "U$3") (pin "17") (pinfunction "NSLEEP_17") (pintype "bidirectional"))
    )
    (net (code "31") (name "Net-(JP12-Pad1)") (class "Default")
      (node (ref "JP12") (pin "1") (pinfunction "1_1") (pintype "passive"))
      (node (ref "R18") (pin "1") (pinfunction "1_1") (pintype "passive"))
    )
    (net (code "32") (name "Net-(JP13-Pad1)") (class "Default")
      (node (ref "JP13") (pin "1") (pinfunction "1_1") (pintype "passive"))
      (node (ref "R19") (pin "1") (pinfunction "1_1") (pintype "passive"))
    )
    (net (code "33") (name "Net-(LED1-PadA)") (class "Default")
      (node (ref "LED1") (pin "A") (pinfunction "A_A") (pintype "passive"))
      (node (ref "R3") (pin "1") (pinfunction "1_1") (pintype "passive"))
    )
    (net (code "34") (name "Net-(LED2-PadA)") (class "Default")
      (node (ref "LED2") (pin "A") (pinfunction "A_A") (pintype "passive"))
      (node (ref "R2") (pin "1") (pinfunction "1_1") (pintype "passive"))
    )
    (net (code "35") (name "Net-(LED3-PadA)") (class "Default")
      (node (ref "LED3") (pin "A") (pinfunction "A_A") (pintype "passive"))
      (node (ref "R1") (pin "1") (pinfunction "1_1") (pintype "passive"))
    )
    (net (code "36") (name "Net-(LED4-PadA)") (class "Default")
      (node (ref "LED4") (pin "A") (pinfunction "A_A") (pintype "passive"))
      (node (ref "R21") (pin "1") (pinfunction "1_1") (pintype "passive"))
    )
    (net (code "37") (name "Net-(LED5-PadA)") (class "Default")
      (node (ref "LED5") (pin "A") (pinfunction "A_A") (pintype "passive"))
      (node (ref "R20") (pin "1") (pinfunction "1_1") (pintype "passive"))
    )
    (net (code "38") (name "Net-(TOUCH_RESET-P2)") (class "Default")
      (node (ref "C3") (pin "1") (pinfunction "1_1") (pintype "passive"))
      (node (ref "JP11") (pin "1") (pinfunction "1_1") (pintype "passive"))
      (node (ref "R4") (pin "2") (pinfunction "2_2") (pintype "passive"))
      (node (ref "R5") (pin "1") (pinfunction "1_1") (pintype "passive"))
      (node (ref "TOUCH_RESET") (pin "P$2") (pinfunction "P2_P$2") (pintype "bidirectional"))
      (node (ref "TOUCH_RESET") (pin "P$3") (pinfunction "P3_P$3") (pintype "bidirectional"))
    )
    (net (code "39") (name "Net-(U$2-AISEN)") (class "Default")
      (node (ref "R6") (pin "1") (pinfunction "1_1") (pintype "passive"))
      (node (ref "U$2") (pin "6") (pinfunction "AISEN_6") (pintype "bidirectional"))
    )
    (net (code "40") (name "Net-(U$2-AVREF)") (class "Default")
      (node (ref "R8") (pin "2") (pinfunction "2_2") (pintype "passive"))
      (node (ref "R9") (pin "1") (pinfunction "1_1") (pintype "passive"))
      (node (ref "U$2") (pin "13") (pinfunction "AVREF_13") (pintype "bidirectional"))
      (node (ref "U$2") (pin "14") (pinfunction "BVREF_14") (pintype "bidirectional"))
    )
    (net (code "41") (name "Net-(U$2-BISEN)") (class "Default")
      (node (ref "R7") (pin "1") (pinfunction "1_1") (pintype "passive"))
      (node (ref "U$2") (pin "9") (pinfunction "BISEN_9") (pintype "bidirectional"))
    )
    (net (code "42") (name "Net-(U$2-CPH)") (class "Default")
      (node (ref "C7") (pin "2") (pinfunction "2_2") (pintype "passive"))
      (node (ref "U$2") (pin "2") (pinfunction "CPH_2") (pintype "bidirectional"))
    )
    (net (code "43") (name "Net-(U$2-CPL)") (class "Default")
      (node (ref "C7") (pin "1") (pinfunction "1_1") (pintype "passive"))
      (node (ref "U$2") (pin "1") (pinfunction "CPL_1") (pintype "bidirectional"))
    )
    (net (code "44") (name "Net-(U$2-VCP)") (class "Default")
      (node (ref "C8") (pin "1") (pinfunction "1_1") (pintype "passive"))
      (node (ref "U$2") (pin "3") (pinfunction "VCP_3") (pintype "bidirectional"))
    )
    (net (code "45") (name "Net-(U$3-AISEN)") (class "Default")
      (node (ref "R11") (pin "1") (pinfunction "1_1") (pintype "passive"))
      (node (ref "U$3") (pin "6") (pinfunction "AISEN_6") (pintype "bidirectional"))
    )
    (net (code "46") (name "Net-(U$3-AVREF)") (class "Default")
      (node (ref "R13") (pin "2") (pinfunction "2_2") (pintype "passive"))
      (node (ref "R14") (pin "1") (pinfunction "1_1") (pintype "passive"))
      (node (ref "U$3") (pin "13") (pinfunction "AVREF_13") (pintype "bidirectional"))
      (node (ref "U$3") (pin "14") (pinfunction "BVREF_14") (pintype "bidirectional"))
    )
    (net (code "47") (name "Net-(U$3-BISEN)") (class "Default")
      (node (ref "R12") (pin "1") (pinfunction "1_1") (pintype "passive"))
      (node (ref "U$3") (pin "9") (pinfunction "BISEN_9") (pintype "bidirectional"))
    )
    (net (code "48") (name "Net-(U$3-CPH)") (class "Default")
      (node (ref "C13") (pin "2") (pinfunction "2_2") (pintype "passive"))
      (node (ref "U$3") (pin "2") (pinfunction "CPH_2") (pintype "bidirectional"))
    )
    (net (code "49") (name "Net-(U$3-CPL)") (class "Default")
      (node (ref "C13") (pin "1") (pinfunction "1_1") (pintype "passive"))
      (node (ref "U$3") (pin "1") (pinfunction "CPL_1") (pintype "bidirectional"))
    )
    (net (code "50") (name "Net-(U$3-VCP)") (class "Default")
      (node (ref "C14") (pin "1") (pinfunction "1_1") (pintype "passive"))
      (node (ref "U$3") (pin "3") (pinfunction "VCP_3") (pintype "bidirectional"))
    )
    (net (code "51") (name "OUT0") (class "Default")
      (node (ref "IC1") (pin "36") (pinfunction "RC2/AN14/CCP1_36") (pintype "bidirectional"))
      (node (ref "OUT0") (pin "3") (pinfunction "3_3") (pintype "passive"))
    )
    (net (code "52") (name "OUT1") (class "Default")
      (node (ref "IC1") (pin "37") (pinfunction "RC3/AN15/SCK/SCL_37") (pintype "bidirectional"))
      (node (ref "OUT1") (pin "3") (pinfunction "3_3") (pintype "passive"))
    )
    (net (code "53") (name "OUT2") (class "Default")
      (node (ref "IC1") (pin "38") (pinfunction "RD0/AN20_38") (pintype "bidirectional"))
      (node (ref "OUT2") (pin "3") (pinfunction "3_3") (pintype "passive"))
    )
    (net (code "54") (name "OUT3") (class "Default")
      (node (ref "IC1") (pin "39") (pinfunction "RD1/AN21_39") (pintype "bidirectional"))
      (node (ref "OUT3") (pin "3") (pinfunction "3_3") (pintype "passive"))
    )
    (net (code "55") (name "OUT4") (class "Default")
      (node (ref "IC1") (pin "40") (pinfunction "RD2/AN22_40") (pintype "bidirectional"))
      (node (ref "OUT4") (pin "3") (pinfunction "3_3") (pintype "passive"))
    )
    (net (code "56") (name "OUT5") (class "Default")
      (node (ref "IC1") (pin "41") (pinfunction "RD3/AN23_41") (pintype "bidirectional"))
      (node (ref "OUT5") (pin "3") (pinfunction "3_3") (pintype "passive"))
    )
    (net (code "57") (name "OUT6") (class "Default")
      (node (ref "IC1") (pin "42") (pinfunction "RC4/AN16/SDI/SDA_42") (pintype "bidirectional"))
      (node (ref "OUT6") (pin "3") (pinfunction "3_3") (pintype "passive"))
    )
    (net (code "58") (name "OUT7") (class "Default")
      (node (ref "IC1") (pin "43") (pinfunction "RC5/AN17/SDO_43") (pintype "bidirectional"))
      (node (ref "OUT7") (pin "3") (pinfunction "3_3") (pintype "passive"))
    )
    (net (code "59") (name "OUT8") (class "Default")
      (node (ref "IC1") (pin "44") (pinfunction "RC6/AN18/TX/CK_44") (pintype "bidirectional"))
      (node (ref "OUT8") (pin "3") (pinfunction "3_3") (pintype "passive"))
    )
    (net (code "60") (name "OUT9") (class "Default")
      (node (ref "IC1") (pin "1") (pinfunction "DT/RX/AN19/RC7_1") (pintype "bidirectional"))
      (node (ref "OUT9") (pin "3") (pinfunction "3_3") (pintype "passive"))
    )
    (net (code "61") (name "QEIA1_1") (class "Default")
      (node (ref "IC1") (pin "20") (pinfunction "AN1/RA1_20") (pintype "bidirectional"))
      (node (ref "MOTORA_1") (pin "5") (pinfunction "S_5") (pintype "passive"))
    )
    (net (code "62") (name "QEIA1_2") (class "Default")
      (node (ref "IC1") (pin "19") (pinfunction "~{SS}/AN0/RA0_19") (pintype "bidirectional"))
      (node (ref "MOTORA_1") (pin "6") (pinfunction "S_6") (pintype "passive"))
    )
    (net (code "63") (name "QEIA2_1") (class "Default")
      (node (ref "IC1") (pin "24") (pinfunction "RA5/AN4/~{SS}/VCAP_24") (pintype "bidirectional"))
      (node (ref "MOTORA_2") (pin "5") (pinfunction "S_5") (pintype "passive"))
    )
    (net (code "64") (name "QEIA2_2") (class "Default")
      (node (ref "IC1") (pin "23") (pinfunction "RA4/TOCKI_23") (pintype "bidirectional"))
      (node (ref "MOTORA_2") (pin "6") (pinfunction "S_6") (pintype "passive"))
    )
    (net (code "65") (name "QEIB1_1") (class "Default")
      (node (ref "IC1") (pin "22") (pinfunction "VREF+/AN3/RA3_22") (pintype "bidirectional"))
      (node (ref "MOTORB_1") (pin "5") (pinfunction "S_5") (pintype "passive"))
    )
    (net (code "66") (name "QEIB1_2") (class "Default")
      (node (ref "IC1") (pin "21") (pinfunction "AN2/RA2_21") (pintype "bidirectional"))
      (node (ref "MOTORB_1") (pin "6") (pinfunction "S_6") (pintype "passive"))
    )
    (net (code "67") (name "QEIB2_1") (class "Default")
      (node (ref "IC1") (pin "31") (pinfunction "RA6/OSC2/CLKOUT_31") (pintype "bidirectional"))
      (node (ref "MOTORB_2") (pin "5") (pinfunction "S_5") (pintype "passive"))
    )
    (net (code "68") (name "QEIB2_2") (class "Default")
      (node (ref "IC1") (pin "30") (pinfunction "RA7/OSC1/CLKIN_30") (pintype "bidirectional"))
      (node (ref "MOTORB_2") (pin "6") (pinfunction "S_6") (pintype "passive"))
    )
    (net (code "69") (name "SCL") (class "Default")
      (node (ref "IC1") (pin "35") (pinfunction "RC1/SOSCI/CCP2_35") (pintype "bidirectional"))
      (node (ref "JP2") (pin "2") (pinfunction "2_2") (pintype "passive"))
      (node (ref "R16") (pin "2") (pinfunction "2_2") (pintype "passive"))
      (node (ref "X1") (pin "5") (pinfunction "SCL_5") (pintype "bidirectional"))
    )
    (net (code "70") (name "SDA") (class "Default")
      (node (ref "IC1") (pin "32") (pinfunction "RC0/SOSCO/T1CKI_32") (pintype "bidirectional"))
      (node (ref "JP2") (pin "1") (pinfunction "1_1") (pintype "passive"))
      (node (ref "R17") (pin "1") (pinfunction "1_1") (pintype "passive"))
      (node (ref "X1") (pin "3") (pinfunction "SDA_3") (pintype "bidirectional"))
    )
    (net (code "71") (name "STATUS1") (class "Default")
      (node (ref "IC1") (pin "25") (pinfunction "RE0/AN5_25") (pintype "bidirectional"))
      (node (ref "R1") (pin "2") (pinfunction "2_2") (pintype "passive"))
    )
    (net (code "72") (name "TRQ0") (class "Default")
      (node (ref "JP1") (pin "3") (pinfunction "3_3") (pintype "passive"))
      (node (ref "U$2") (pin "27") (pinfunction "TRQ0_27") (pintype "bidirectional"))
      (node (ref "U$3") (pin "27") (pinfunction "TRQ0_27") (pintype "bidirectional"))
    )
    (net (code "73") (name "TRQ1") (class "Default")
      (node (ref "JP1") (pin "4") (pinfunction "4_4") (pintype "passive"))
      (node (ref "U$2") (pin "26") (pinfunction "TRQ1_26") (pintype "bidirectional"))
      (node (ref "U$3") (pin "26") (pinfunction "TRQ1_26") (pintype "bidirectional"))
    )
    (net (code "74") (name "V3P3_1") (class "Default")
      (node (ref "C11") (pin "1") (pinfunction "1_1") (pintype "passive"))
      (node (ref "R10") (pin "2") (pinfunction "2_2") (pintype "passive"))
      (node (ref "R8") (pin "1") (pinfunction "1_1") (pintype "passive"))
      (node (ref "U$2") (pin "15") (pinfunction "V3P3_15") (pintype "bidirectional"))
    )
    (net (code "75") (name "V3P3_2") (class "Default")
      (node (ref "C17") (pin "1") (pinfunction "1_1") (pintype "passive"))
      (node (ref "R13") (pin "1") (pinfunction "1_1") (pintype "passive"))
      (node (ref "R15") (pin "2") (pinfunction "2_2") (pintype "passive"))
      (node (ref "U$3") (pin "15") (pinfunction "V3P3_15") (pintype "bidirectional"))
    )
    (net (code "76") (name "unconnected-(JP11-Pad6)") (class "Default")
      (node (ref "JP11") (pin "6") (pinfunction "6_6") (pintype "passive"))
    )
    (net (code "77") (name "unconnected-(U$2-ADECAY-Pad20)") (class "Default")
      (node (ref "U$2") (pin "20") (pinfunction "ADECAY_20") (pintype "bidirectional"))
    )
    (net (code "78") (name "unconnected-(U$2-BDECAY-Pad19)") (class "Default")
      (node (ref "U$2") (pin "19") (pinfunction "BDECAY_19") (pintype "bidirectional"))
    )
    (net (code "79") (name "unconnected-(U$2-TOFF-Pad16)") (class "Default")
      (node (ref "U$2") (pin "16") (pinfunction "TOFF_16") (pintype "bidirectional"))
    )
    (net (code "80") (name "unconnected-(U$3-ADECAY-Pad20)") (class "Default")
      (node (ref "U$3") (pin "20") (pinfunction "ADECAY_20") (pintype "bidirectional"))
    )
    (net (code "81") (name "unconnected-(U$3-BDECAY-Pad19)") (class "Default")
      (node (ref "U$3") (pin "19") (pinfunction "BDECAY_19") (pintype "bidirectional"))
    )
    (net (code "82") (name "unconnected-(U$3-TOFF-Pad16)") (class "Default")
      (node (ref "U$3") (pin "16") (pinfunction "TOFF_16") (pintype "bidirectional"))
    )
    (net (code "83") (name "unconnected-(X1-GPIO04-Pad7)") (class "Default")
      (node (ref "X1") (pin "7") (pinfunction "GPIO04_7") (pintype "bidirectional"))
    )
    (net (code "84") (name "unconnected-(X1-GPIO05-Pad29)") (class "Default")
      (node (ref "X1") (pin "29") (pinfunction "GPIO05_29") (pintype "no_connect"))
    )
    (net (code "85") (name "unconnected-(X1-GPIO06-Pad31)") (class "Default")
      (node (ref "X1") (pin "31") (pinfunction "GPIO06_31") (pintype "no_connect"))
    )
    (net (code "86") (name "unconnected-(X1-GPIO12-Pad32)") (class "Default")
      (node (ref "X1") (pin "32") (pinfunction "GPIO12_32") (pintype "no_connect"))
    )
    (net (code "87") (name "unconnected-(X1-GPIO13-Pad33)") (class "Default")
      (node (ref "X1") (pin "33") (pinfunction "GPIO13_33") (pintype "no_connect"))
    )
    (net (code "88") (name "unconnected-(X1-GPIO16-Pad36)") (class "Default")
      (node (ref "X1") (pin "36") (pinfunction "GPIO16_36") (pintype "no_connect"))
    )
    (net (code "89") (name "unconnected-(X1-GPIO17-Pad11)") (class "Default")
      (node (ref "X1") (pin "11") (pinfunction "GPIO17_11") (pintype "bidirectional"))
    )
    (net (code "90") (name "unconnected-(X1-GPIO18-Pad12)") (class "Default")
      (node (ref "X1") (pin "12") (pinfunction "GPIO18_12") (pintype "bidirectional"))
    )
    (net (code "91") (name "unconnected-(X1-GPIO19-Pad35)") (class "Default")
      (node (ref "X1") (pin "35") (pinfunction "GPIO19_35") (pintype "no_connect"))
    )
    (net (code "92") (name "unconnected-(X1-GPIO20-Pad38)") (class "Default")
      (node (ref "X1") (pin "38") (pinfunction "GPIO20_38") (pintype "no_connect"))
    )
    (net (code "93") (name "unconnected-(X1-GPIO21-Pad40)") (class "Default")
      (node (ref "X1") (pin "40") (pinfunction "GPIO21_40") (pintype "no_connect"))
    )
    (net (code "94") (name "unconnected-(X1-GPIO22-Pad15)") (class "Default")
      (node (ref "X1") (pin "15") (pinfunction "GPIO22_15") (pintype "bidirectional"))
    )
    (net (code "95") (name "unconnected-(X1-GPIO23-Pad16)") (class "Default")
      (node (ref "X1") (pin "16") (pinfunction "GPIO23_16") (pintype "bidirectional"))
    )
    (net (code "96") (name "unconnected-(X1-GPIO24-Pad18)") (class "Default")
      (node (ref "X1") (pin "18") (pinfunction "GPIO24_18") (pintype "bidirectional"))
    )
    (net (code "97") (name "unconnected-(X1-GPIO25-Pad22)") (class "Default")
      (node (ref "X1") (pin "22") (pinfunction "GPIO25_22") (pintype "bidirectional"))
    )
    (net (code "98") (name "unconnected-(X1-GPIO26-Pad37)") (class "Default")
      (node (ref "X1") (pin "37") (pinfunction "GPIO26_37") (pintype "no_connect"))
    )
    (net (code "99") (name "unconnected-(X1-GPIO27-Pad13)") (class "Default")
      (node (ref "X1") (pin "13") (pinfunction "GPIO27_13") (pintype "bidirectional"))
    )
    (net (code "100") (name "unconnected-(X1-ID_SC-Pad28)") (class "Default")
      (node (ref "X1") (pin "28") (pinfunction "ID_SC_28") (pintype "no_connect"))
    )
    (net (code "101") (name "unconnected-(X1-ID_SD-Pad27)") (class "Default")
      (node (ref "X1") (pin "27") (pinfunction "ID_SD_27") (pintype "no_connect"))
    )
    (net (code "102") (name "unconnected-(X1-RXD-Pad10)") (class "Default")
      (node (ref "X1") (pin "10") (pinfunction "RXD_10") (pintype "bidirectional"))
    )
    (net (code "103") (name "unconnected-(X1-SPI_CE0-Pad24)") (class "Default")
      (node (ref "X1") (pin "24") (pinfunction "SPI_CE0_24") (pintype "bidirectional"))
    )
    (net (code "104") (name "unconnected-(X1-SPI_CE1-Pad26)") (class "Default")
      (node (ref "X1") (pin "26") (pinfunction "SPI_CE1_26") (pintype "bidirectional"))
    )
    (net (code "105") (name "unconnected-(X1-SPI_MISO-Pad21)") (class "Default")
      (node (ref "X1") (pin "21") (pinfunction "SPI_MISO_21") (pintype "bidirectional"))
    )
    (net (code "106") (name "unconnected-(X1-SPI_MOSI-Pad19)") (class "Default")
      (node (ref "X1") (pin "19") (pinfunction "SPI_MOSI_19") (pintype "bidirectional"))
    )
    (net (code "107") (name "unconnected-(X1-SPI_SCLK-Pad23)") (class "Default")
      (node (ref "X1") (pin "23") (pinfunction "SPI_SCLK_23") (pintype "bidirectional"))
    )
    (net (code "108") (name "unconnected-(X1-TXD-Pad8)") (class "Default")
      (node (ref "X1") (pin "8") (pinfunction "TXD_8") (pintype "bidirectional"))
    )
  )
)
